# microBoard_HMI.net
KiCad netlist of a schematic drawn in EAGLE
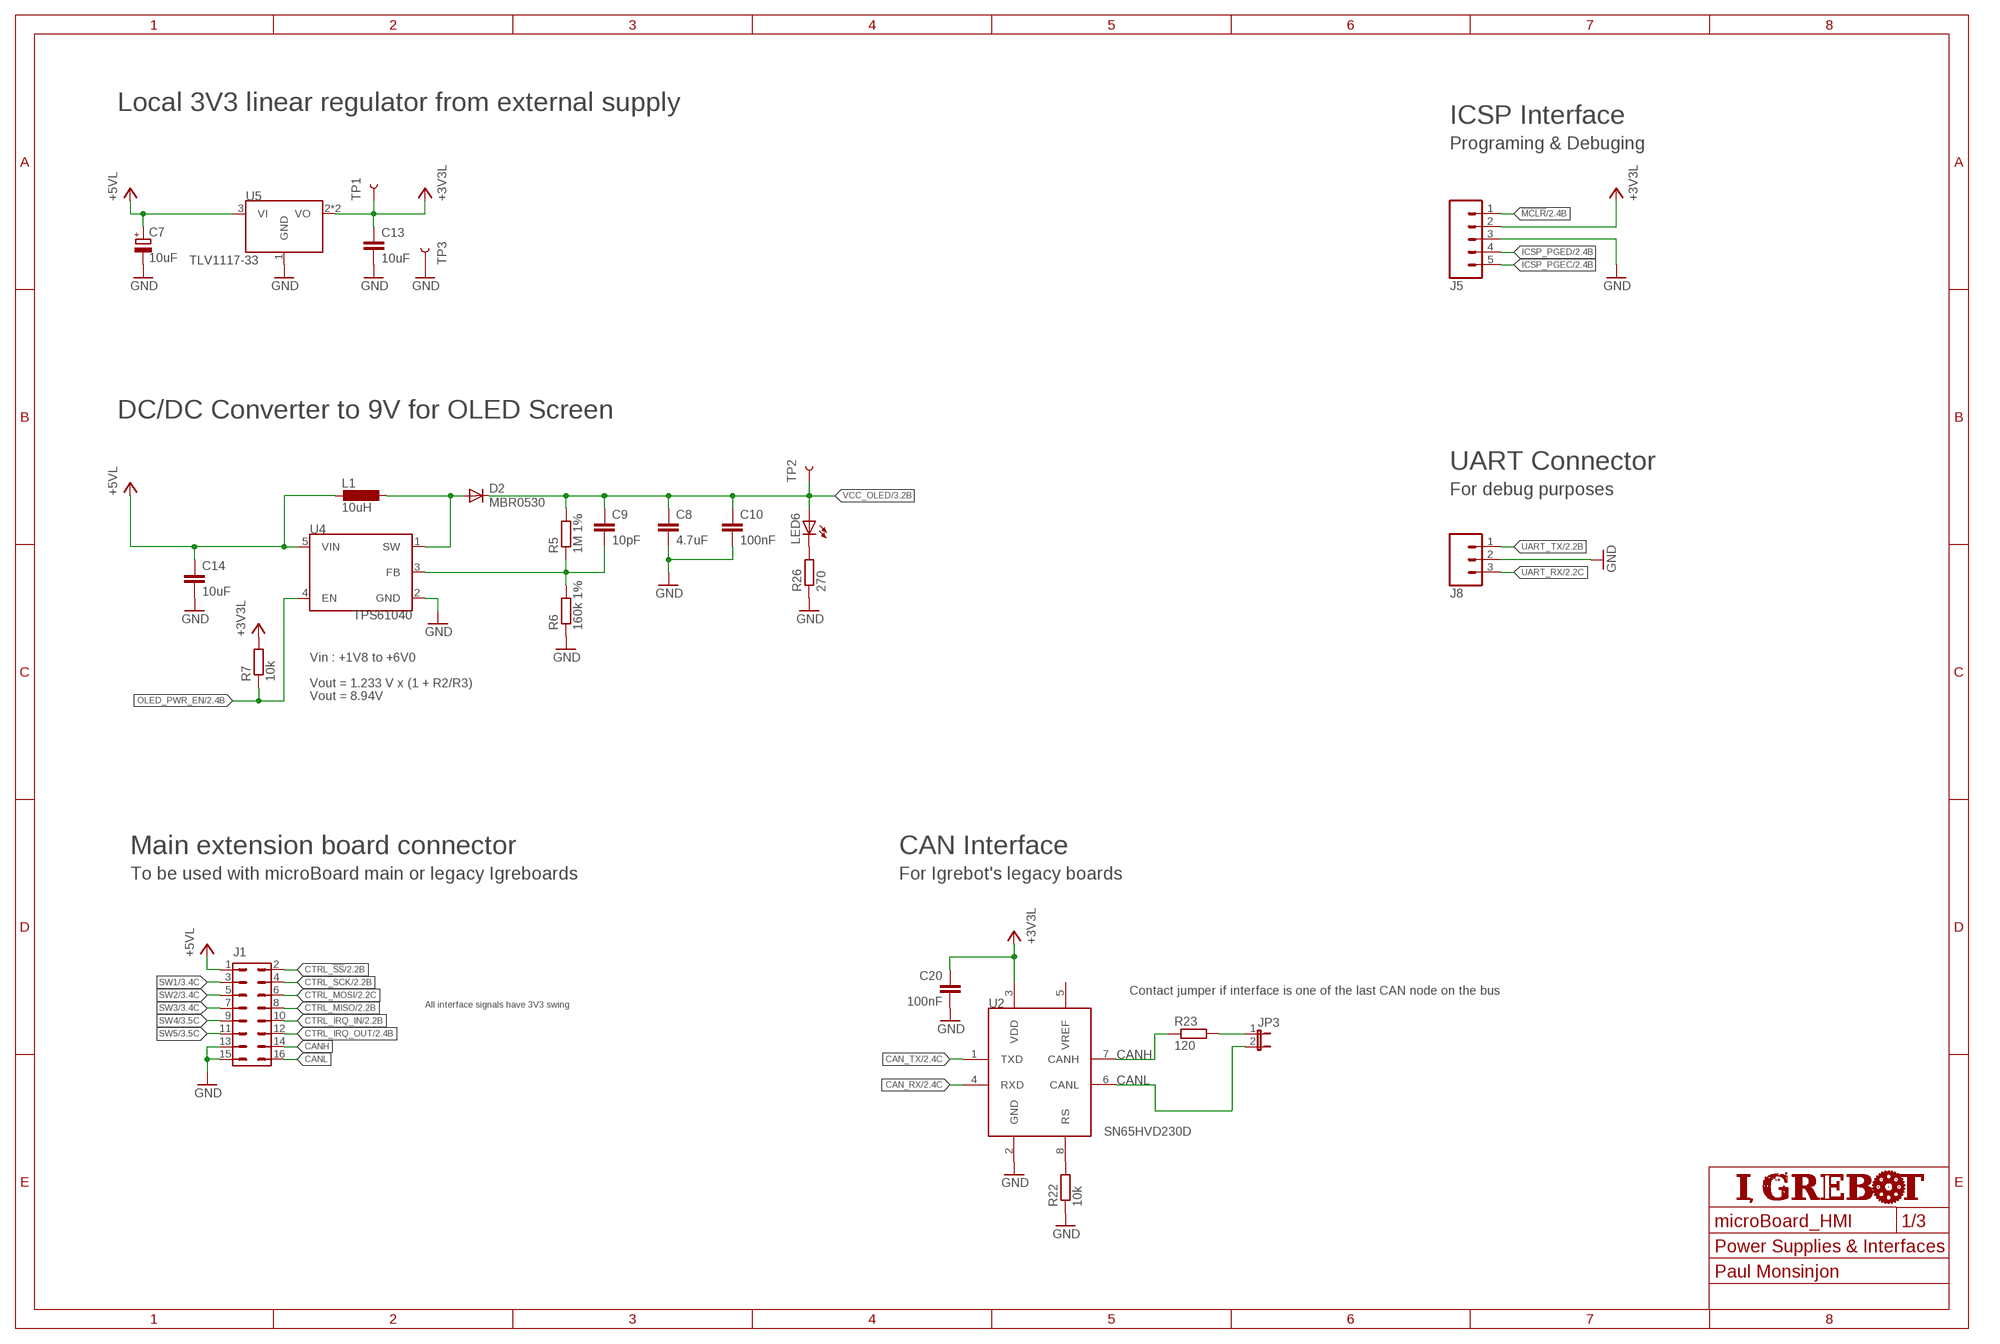
[diagram p0: schematic, sheet 1]
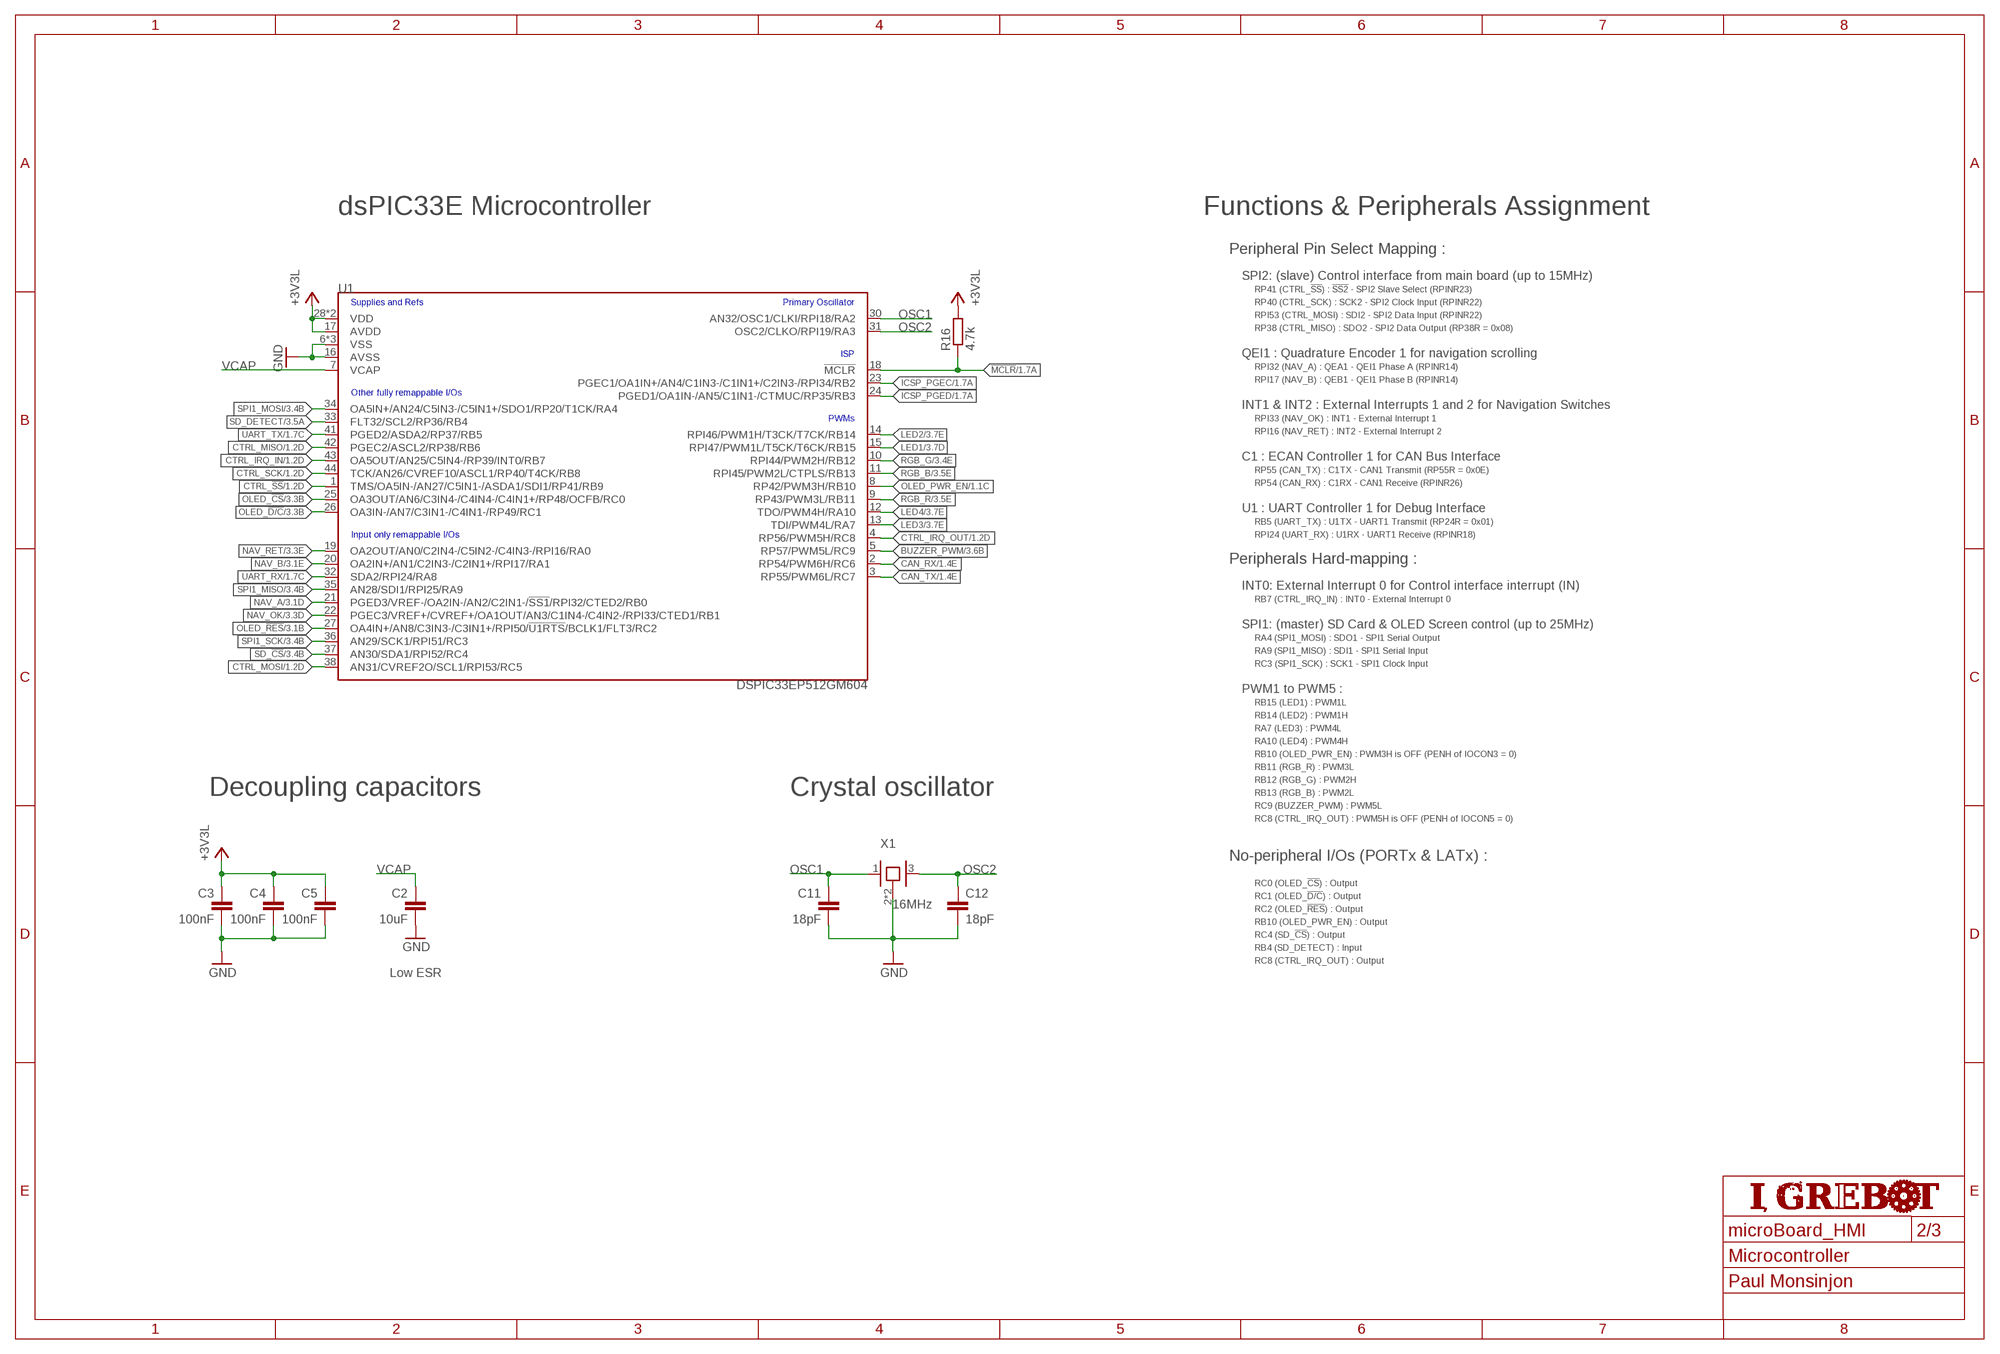
[diagram p1: schematic, sheet 2]
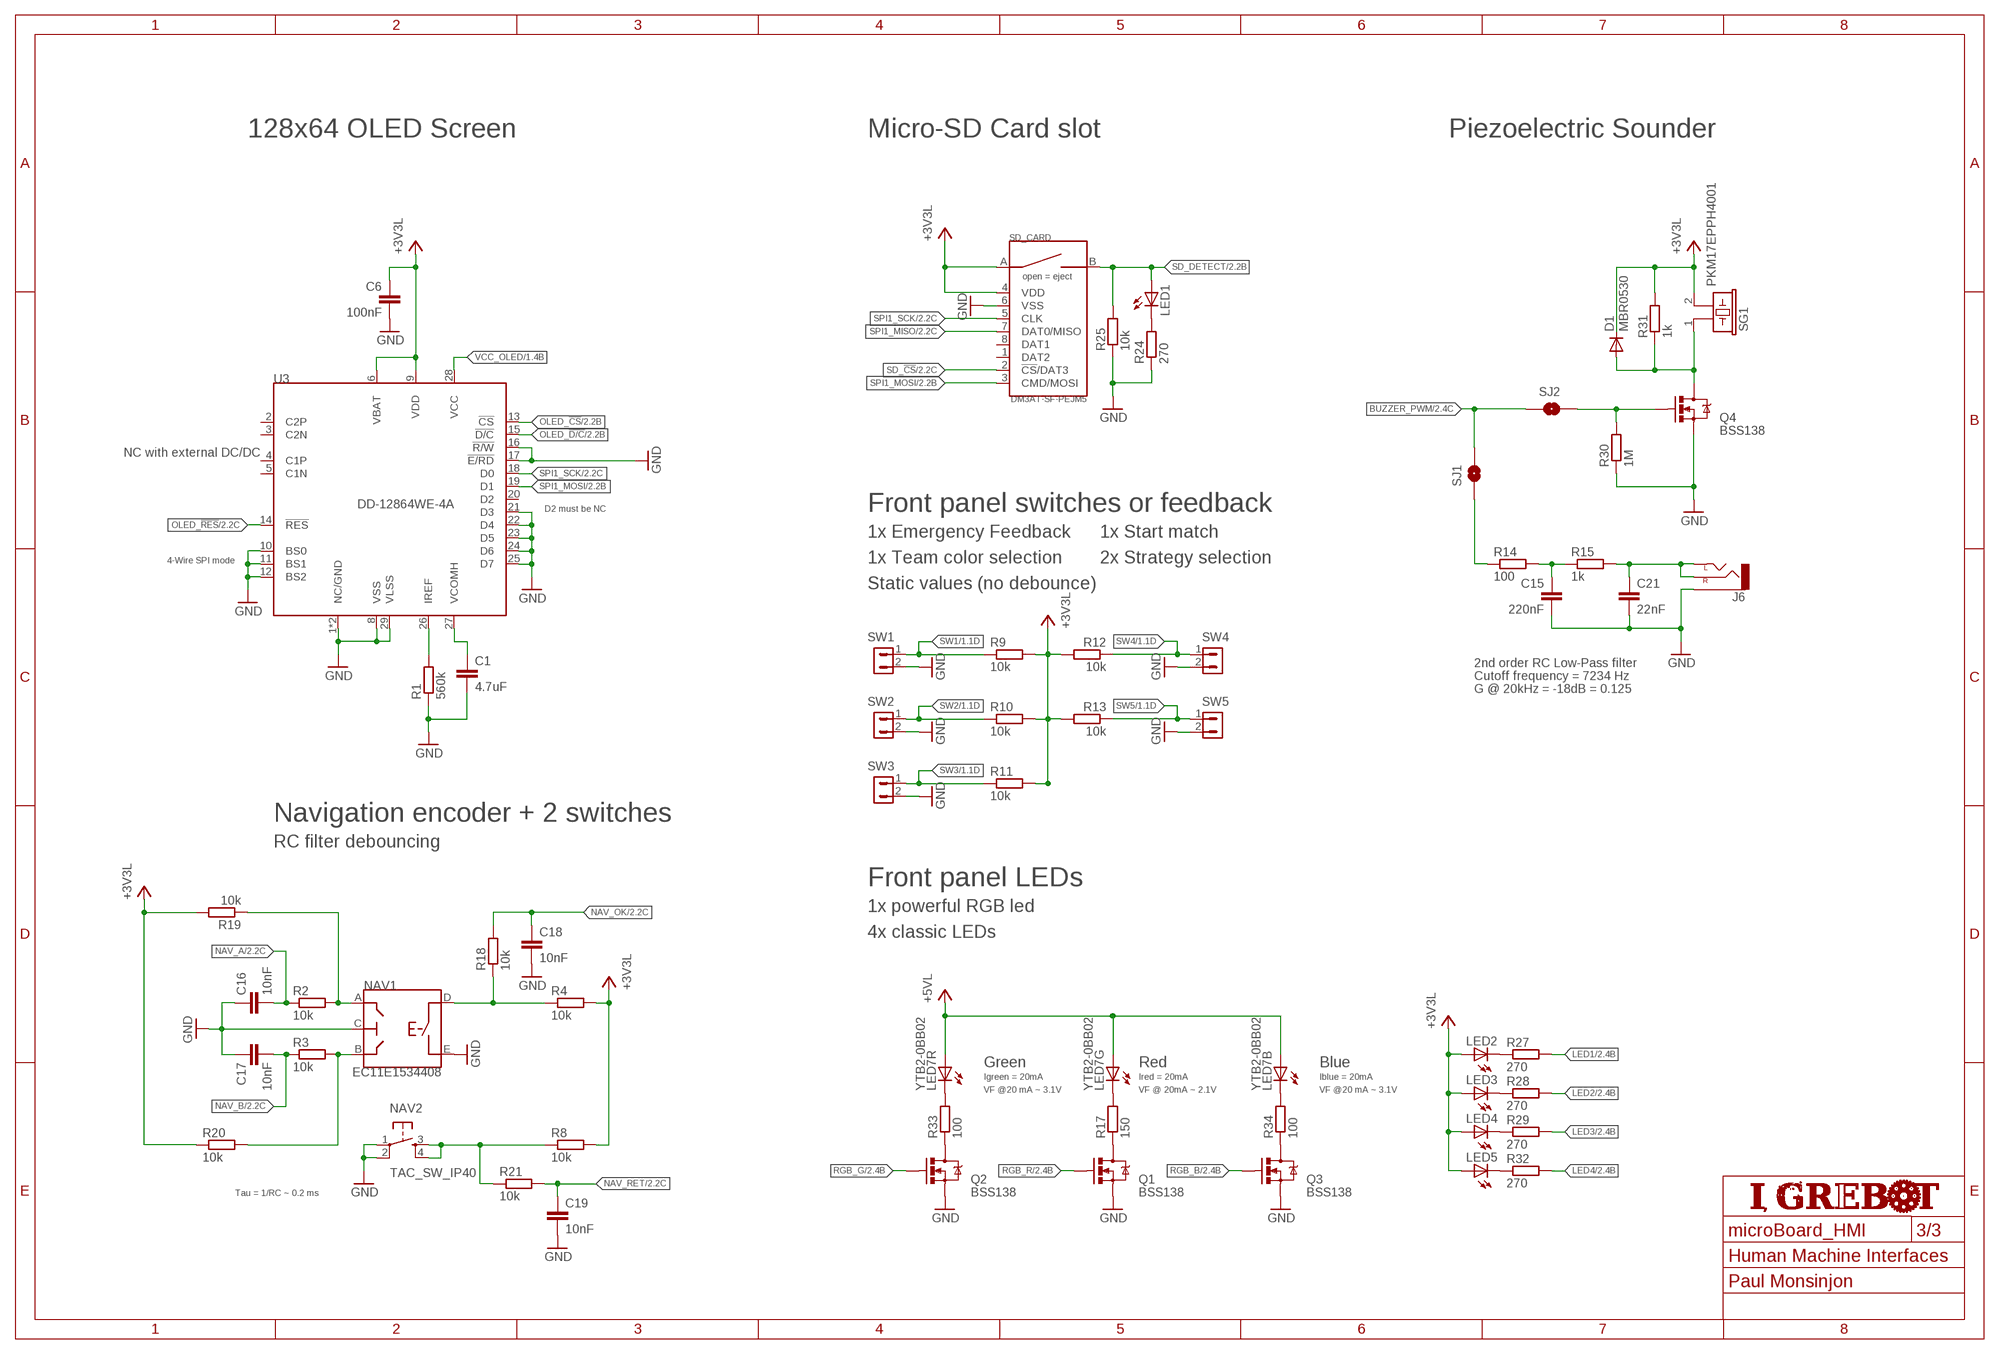
[diagram p2: schematic, sheet 3]

(export (version "E")
  (design (tool "Eeschema 10.0.6"))
  (components
    (comp (ref "C2")
      (value "10uF")
      (footprint "eagle-import:C1206")
      (libsource (lib "eagle-import") (part "C-EUC1206"))
    )
    (comp (ref "C3")
      (value "100nF")
      (footprint "eagle-import:C0603")
      (libsource (lib "eagle-import") (part "C-EUC0603"))
    )
    (comp (ref "C4")
      (value "100nF")
      (footprint "eagle-import:C0603")
      (libsource (lib "eagle-import") (part "C-EUC0603"))
    )
    (comp (ref "C5")
      (value "100nF")
      (footprint "eagle-import:C0603")
      (libsource (lib "eagle-import") (part "C-EUC0603"))
    )
    (comp (ref "C11")
      (value "18pF")
      (footprint "eagle-import:C0603")
      (libsource (lib "eagle-import") (part "C-EUC0603"))
    )
    (comp (ref "C12")
      (value "18pF")
      (footprint "eagle-import:C0603")
      (libsource (lib "eagle-import") (part "C-EUC0603"))
    )
    (comp (ref "R16")
      (value "4.7k")
      (footprint "eagle-import:R0603")
      (libsource (lib "eagle-import") (part "resistor_R-EU_R0603"))
    )
    (comp (ref "U1")
      (value "DSPIC33EP512GM604")
      (footprint "eagle-import:TQFP_44")
      (libsource (lib "eagle-import") (part "DSPIC33EP512GM604"))
    )
    (comp (ref "X1")
      (value "16MHz")
      (footprint "eagle-import:CRYSTAL-OSC-SMD-5X3")
      (libsource (lib "eagle-import") (part "XTAL_5X3"))
    )
    (comp (ref "C1")
      (value "4.7uF")
      (footprint "eagle-import:C1206")
      (libsource (lib "eagle-import") (part "C-EUC1206"))
    )
    (comp (ref "C6")
      (value "100nF")
      (footprint "eagle-import:C0603")
      (libsource (lib "eagle-import") (part "C-EUC0603"))
    )
    (comp (ref "C15")
      (value "220nF")
      (footprint "eagle-import:C0603")
      (libsource (lib "eagle-import") (part "C-EUC0603"))
    )
    (comp (ref "C16")
      (value "10nF")
      (footprint "eagle-import:C0603")
      (libsource (lib "eagle-import") (part "C-EUC0603"))
    )
    (comp (ref "C17")
      (value "10nF")
      (footprint "eagle-import:C0603")
      (libsource (lib "eagle-import") (part "C-EUC0603"))
    )
    (comp (ref "C18")
      (value "10nF")
      (footprint "eagle-import:C0603")
      (libsource (lib "eagle-import") (part "C-EUC0603"))
    )
    (comp (ref "C19")
      (value "10nF")
      (footprint "eagle-import:C0603")
      (libsource (lib "eagle-import") (part "C-EUC0603"))
    )
    (comp (ref "C21")
      (value "22nF")
      (footprint "eagle-import:C0603")
      (libsource (lib "eagle-import") (part "C-EUC0603"))
    )
    (comp (ref "D1")
      (value "MBR0530")
      (footprint "eagle-import:SOD-123_MINI-SMA")
      (libsource (lib "eagle-import") (part "CGRM400-G1"))
    )
    (comp (ref "J6")
      (value "AUDIO-JACK1:1")
      (footprint "eagle-import:STEREOJACK2.5MM")
      (libsource (lib "eagle-import") (part "AUDIO-JACK1{colon}1"))
    )
    (comp (ref "LED1")
      (value "LEDCHIP-LED0805")
      (footprint "eagle-import:CHIP-LED0805")
      (libsource (lib "eagle-import") (part "LEDCHIP-LED0805"))
    )
    (comp (ref "LED2")
      (value "LEDCHIP-LED0805")
      (footprint "eagle-import:CHIP-LED0805")
      (libsource (lib "eagle-import") (part "LEDCHIP-LED0805"))
    )
    (comp (ref "LED3")
      (value "LEDCHIP-LED0805")
      (footprint "eagle-import:CHIP-LED0805")
      (libsource (lib "eagle-import") (part "LEDCHIP-LED0805"))
    )
    (comp (ref "LED4")
      (value "LEDCHIP-LED0805")
      (footprint "eagle-import:CHIP-LED0805")
      (libsource (lib "eagle-import") (part "LEDCHIP-LED0805"))
    )
    (comp (ref "LED5")
      (value "LEDCHIP-LED0805")
      (footprint "eagle-import:CHIP-LED0805")
      (libsource (lib "eagle-import") (part "LEDCHIP-LED0805"))
    )
    (comp (ref "LED7")
      (value "YTB2-0BB02")
      (footprint "eagle-import:GM5WA94310A")
      (libsource (lib "eagle-import") (part "GM5WA94310A"))
    )
    (comp (ref "NAV1")
      (value "EC11E1534408")
      (footprint "eagle-import:EC11E1534408")
      (libsource (lib "eagle-import") (part "EC11E1534408"))
    )
    (comp (ref "NAV2")
      (value "TAC_SW_IP40")
      (footprint "eagle-import:TAC_SW_IP40")
      (libsource (lib "eagle-import") (part "TAC_SW_IP40"))
    )
    (comp (ref "Q1")
      (value "BSS138")
      (footprint "eagle-import:SOT23")
      (libsource (lib "eagle-import") (part "MOSFET-NCHANNELBSS138"))
    )
    (comp (ref "Q2")
      (value "BSS138")
      (footprint "eagle-import:SOT23")
      (libsource (lib "eagle-import") (part "MOSFET-NCHANNELBSS138"))
    )
    (comp (ref "Q3")
      (value "BSS138")
      (footprint "eagle-import:SOT23")
      (libsource (lib "eagle-import") (part "MOSFET-NCHANNELBSS138"))
    )
    (comp (ref "Q4")
      (value "BSS138")
      (footprint "eagle-import:SOT23")
      (fields (field (name "PROD_ID") "TRANS-00830"))
      (libsource (lib "eagle-import") (part "MOSFET-NCHANNELBSS138"))
    )
    (comp (ref "R1")
      (value "560k")
      (footprint "eagle-import:R0603")
      (libsource (lib "eagle-import") (part "R-EU_R0603"))
    )
    (comp (ref "R2")
      (value "10k")
      (footprint "eagle-import:R0603")
      (libsource (lib "eagle-import") (part "R-EU_R0603"))
    )
    (comp (ref "R3")
      (value "10k")
      (footprint "eagle-import:R0603")
      (libsource (lib "eagle-import") (part "R-EU_R0603"))
    )
    (comp (ref "R4")
      (value "10k")
      (footprint "eagle-import:R0603")
      (libsource (lib "eagle-import") (part "R-EU_R0603"))
    )
    (comp (ref "R8")
      (value "10k")
      (footprint "eagle-import:R0603")
      (libsource (lib "eagle-import") (part "R-EU_R0603"))
    )
    (comp (ref "R9")
      (value "10k")
      (footprint "eagle-import:R0603")
      (libsource (lib "eagle-import") (part "R-EU_R0603"))
    )
    (comp (ref "R10")
      (value "10k")
      (footprint "eagle-import:R0603")
      (libsource (lib "eagle-import") (part "R-EU_R0603"))
    )
    (comp (ref "R11")
      (value "10k")
      (footprint "eagle-import:R0603")
      (libsource (lib "eagle-import") (part "R-EU_R0603"))
    )
    (comp (ref "R12")
      (value "10k")
      (footprint "eagle-import:R0603")
      (libsource (lib "eagle-import") (part "R-EU_R0603"))
    )
    (comp (ref "R13")
      (value "10k")
      (footprint "eagle-import:R0603")
      (libsource (lib "eagle-import") (part "R-EU_R0603"))
    )
    (comp (ref "R14")
      (value "100")
      (footprint "eagle-import:R0603")
      (libsource (lib "eagle-import") (part "resistor_R-EU_R0603"))
    )
    (comp (ref "R15")
      (value "1k")
      (footprint "eagle-import:R0603")
      (libsource (lib "eagle-import") (part "resistor_R-EU_R0603"))
    )
    (comp (ref "R17")
      (value "150")
      (footprint "eagle-import:R0603")
      (libsource (lib "eagle-import") (part "resistor_R-EU_R0603"))
    )
    (comp (ref "R18")
      (value "10k")
      (footprint "eagle-import:R0603")
      (libsource (lib "eagle-import") (part "R-EU_R0603"))
    )
    (comp (ref "R19")
      (value "10k")
      (footprint "eagle-import:R0603")
      (libsource (lib "eagle-import") (part "R-EU_R0603"))
    )
    (comp (ref "R20")
      (value "10k")
      (footprint "eagle-import:R0603")
      (libsource (lib "eagle-import") (part "R-EU_R0603"))
    )
    (comp (ref "R21")
      (value "10k")
      (footprint "eagle-import:R0603")
      (libsource (lib "eagle-import") (part "R-EU_R0603"))
    )
    (comp (ref "R24")
      (value "270")
      (footprint "eagle-import:R0603")
      (libsource (lib "eagle-import") (part "resistor_R-EU_R0603"))
    )
    (comp (ref "R25")
      (value "10k")
      (footprint "eagle-import:R0603")
      (libsource (lib "eagle-import") (part "resistor_R-EU_R0603"))
    )
    (comp (ref "R27")
      (value "270")
      (footprint "eagle-import:R0603")
      (libsource (lib "eagle-import") (part "resistor_R-EU_R0603"))
    )
    (comp (ref "R28")
      (value "270")
      (footprint "eagle-import:R0603")
      (libsource (lib "eagle-import") (part "resistor_R-EU_R0603"))
    )
    (comp (ref "R29")
      (value "270")
      (footprint "eagle-import:R0603")
      (libsource (lib "eagle-import") (part "resistor_R-EU_R0603"))
    )
    (comp (ref "R30")
      (value "1M")
      (footprint "eagle-import:R0603")
      (libsource (lib "eagle-import") (part "resistor_R-EU_R0603"))
    )
    (comp (ref "R31")
      (value "1k")
      (footprint "eagle-import:R0603")
      (libsource (lib "eagle-import") (part "resistor_R-EU_R0603"))
    )
    (comp (ref "R32")
      (value "270")
      (footprint "eagle-import:R0603")
      (libsource (lib "eagle-import") (part "resistor_R-EU_R0603"))
    )
    (comp (ref "R33")
      (value "100")
      (footprint "eagle-import:R0603")
      (libsource (lib "eagle-import") (part "resistor_R-EU_R0603"))
    )
    (comp (ref "R34")
      (value "100")
      (footprint "eagle-import:R0603")
      (libsource (lib "eagle-import") (part "resistor_R-EU_R0603"))
    )
    (comp (ref "SD_CARD")
      (value "DM3AT-SF-PEJM5")
      (footprint "eagle-import:DM3AT")
      (libsource (lib "eagle-import") (part "DM3AT-SF-PEJM5"))
    )
    (comp (ref "SG1")
      (value "PKM17EPPH4001")
      (footprint "eagle-import:F_EE17P")
      (libsource (lib "eagle-import") (part "F/EE17P"))
    )
    (comp (ref "SJ1")
      (value "SOLDERJUMPERNC2")
      (footprint "eagle-import:SJ_2S-NOTRACE")
      (libsource (lib "eagle-import") (part "SOLDERJUMPERNC2"))
    )
    (comp (ref "SJ2")
      (value "SOLDERJUMPERNC2")
      (footprint "eagle-import:SJ_2S-NOTRACE")
      (libsource (lib "eagle-import") (part "SOLDERJUMPERNC2"))
    )
    (comp (ref "SW1")
      (value "HE14_H_2")
      (footprint "eagle-import:HE14_H_2")
      (libsource (lib "eagle-import") (part "HE14_H_2"))
    )
    (comp (ref "SW2")
      (value "HE14_H_2")
      (footprint "eagle-import:HE14_H_2")
      (libsource (lib "eagle-import") (part "HE14_H_2"))
    )
    (comp (ref "SW3")
      (value "HE14_H_2")
      (footprint "eagle-import:HE14_H_2")
      (libsource (lib "eagle-import") (part "HE14_H_2"))
    )
    (comp (ref "SW4")
      (value "HE14_H_2")
      (footprint "eagle-import:HE14_H_2")
      (libsource (lib "eagle-import") (part "HE14_H_2"))
    )
    (comp (ref "SW5")
      (value "HE14_H_2")
      (footprint "eagle-import:HE14_H_2")
      (libsource (lib "eagle-import") (part "HE14_H_2"))
    )
    (comp (ref "U3")
      (value "DD-12864WE-4A")
      (footprint "eagle-import:DD-12864WE-4A")
      (libsource (lib "eagle-import") (part "DD-12864WE-4A"))
    )
    (comp (ref "C7")
      (value "10uF")
      (footprint "eagle-import:PANASONIC_C")
      (libsource (lib "eagle-import") (part "CPOL-EUC"))
    )
    (comp (ref "C8")
      (value "4.7uF")
      (footprint "eagle-import:C1206")
      (libsource (lib "eagle-import") (part "C-EUC1206"))
    )
    (comp (ref "C9")
      (value "10pF")
      (footprint "eagle-import:C0603")
      (libsource (lib "eagle-import") (part "C-EUC0603"))
    )
    (comp (ref "C10")
      (value "100nF")
      (footprint "eagle-import:C0603")
      (libsource (lib "eagle-import") (part "C-EUC0603"))
    )
    (comp (ref "C13")
      (value "10uF")
      (footprint "eagle-import:C1206")
      (libsource (lib "eagle-import") (part "C-EUC1206"))
    )
    (comp (ref "C14")
      (value "10uF")
      (footprint "eagle-import:C1206")
      (libsource (lib "eagle-import") (part "C-EUC1206"))
    )
    (comp (ref "C20")
      (value "100nF")
      (footprint "eagle-import:C0603")
      (libsource (lib "eagle-import") (part "C-EUC0603"))
    )
    (comp (ref "D2")
      (value "MBR0530")
      (footprint "eagle-import:SOD-123_MINI-SMA")
      (libsource (lib "eagle-import") (part "CGRM400-G1"))
    )
    (comp (ref "J1")
      (value "HE10_H_16")
      (footprint "eagle-import:CON_2X_2.54_H_16")
      (libsource (lib "eagle-import") (part "HE10_H_16"))
    )
    (comp (ref "J5")
      (value "M05LOCK")
      (footprint "eagle-import:1X05_LOCK")
      (libsource (lib "eagle-import") (part "M05LOCK"))
    )
    (comp (ref "J8")
      (value "M03LOCK")
      (footprint "eagle-import:1X03_LOCK")
      (libsource (lib "eagle-import") (part "M03LOCK"))
    )
    (comp (ref "JP3")
      (value "JUMPER-2PTH_LOCK")
      (footprint "eagle-import:1X02_LOCK")
      (libsource (lib "eagle-import") (part "JUMPER-2PTH_LOCK"))
    )
    (comp (ref "L1")
      (value "10uH")
      (footprint "eagle-import:L5650M")
      (libsource (lib "eagle-import") (part "L-EUL5650M"))
    )
    (comp (ref "LED6")
      (value "LEDCHIP-LED0805")
      (footprint "eagle-import:CHIP-LED0805")
      (libsource (lib "eagle-import") (part "LEDCHIP-LED0805"))
    )
    (comp (ref "R5")
      (value "1M 1%")
      (footprint "eagle-import:R0603")
      (libsource (lib "eagle-import") (part "R-EU_R0603"))
    )
    (comp (ref "R6")
      (value "160k 1%")
      (footprint "eagle-import:R0603")
      (libsource (lib "eagle-import") (part "R-EU_R0603"))
    )
    (comp (ref "R7")
      (value "10k")
      (footprint "eagle-import:R0603")
      (libsource (lib "eagle-import") (part "R-EU_R0603"))
    )
    (comp (ref "R22")
      (value "10k")
      (footprint "eagle-import:R0603")
      (libsource (lib "eagle-import") (part "R-EU_R0603"))
    )
    (comp (ref "R23")
      (value "120")
      (footprint "eagle-import:R0603")
      (libsource (lib "eagle-import") (part "R-EU_R0603"))
    )
    (comp (ref "R26")
      (value "270")
      (footprint "eagle-import:R0603")
      (libsource (lib "eagle-import") (part "resistor_R-EU_R0603"))
    )
    (comp (ref "TP1")
      (value "TEST-POINT3X5")
      (footprint "eagle-import:PAD.03X.05")
      (libsource (lib "eagle-import") (part "TEST-POINT3X5"))
    )
    (comp (ref "TP2")
      (value "TEST-POINT3X5")
      (footprint "eagle-import:PAD.03X.05")
      (libsource (lib "eagle-import") (part "TEST-POINT3X5"))
    )
    (comp (ref "TP3")
      (value "TEST-POINT3X5")
      (footprint "eagle-import:PAD.03X.05")
      (libsource (lib "eagle-import") (part "TEST-POINT3X5"))
    )
    (comp (ref "U2")
      (value "SN65HVD230D")
      (footprint "eagle-import:SO-08")
      (libsource (lib "eagle-import") (part "MCP2551"))
    )
    (comp (ref "U4")
      (value "TPS61040")
      (footprint "eagle-import:SOT-23")
      (libsource (lib "eagle-import") (part "TPS61040"))
    )
    (comp (ref "U5")
      (value "TLV1117-33")
      (footprint "eagle-import:SOT_223")
      (libsource (lib "eagle-import") (part "NX1117C"))
    )
  )
  (nets
    (net (code "1") (name "+3V3L") (class "Default")
      (node (ref "C13") (pin "1") (pinfunction "1_1") (pintype "passive"))
      (node (ref "C20") (pin "1") (pinfunction "1_1") (pintype "passive"))
      (node (ref "C3") (pin "1") (pinfunction "1_1") (pintype "passive"))
      (node (ref "C4") (pin "1") (pinfunction "1_1") (pintype "passive"))
      (node (ref "C5") (pin "1") (pinfunction "1_1") (pintype "passive"))
      (node (ref "C6") (pin "1") (pinfunction "1_1") (pintype "passive"))
      (node (ref "D1") (pin "C") (pinfunction "C_C") (pintype "passive"))
      (node (ref "J5") (pin "2") (pinfunction "2_2") (pintype "passive"))
      (node (ref "LED2") (pin "A") (pinfunction "A_A") (pintype "passive"))
      (node (ref "LED3") (pin "A") (pinfunction "A_A") (pintype "passive"))
      (node (ref "LED4") (pin "A") (pinfunction "A_A") (pintype "passive"))
      (node (ref "LED5") (pin "A") (pinfunction "A_A") (pintype "passive"))
      (node (ref "R10") (pin "2") (pinfunction "2_2") (pintype "passive"))
      (node (ref "R11") (pin "2") (pinfunction "2_2") (pintype "passive"))
      (node (ref "R12") (pin "2") (pinfunction "2_2") (pintype "passive"))
      (node (ref "R13") (pin "2") (pinfunction "2_2") (pintype "passive"))
      (node (ref "R16") (pin "2") (pinfunction "2_2") (pintype "passive"))
      (node (ref "R19") (pin "2") (pinfunction "2_2") (pintype "passive"))
      (node (ref "R20") (pin "1") (pinfunction "1_1") (pintype "passive"))
      (node (ref "R31") (pin "2") (pinfunction "2_2") (pintype "passive"))
      (node (ref "R4") (pin "2") (pinfunction "2_2") (pintype "passive"))
      (node (ref "R7") (pin "2") (pinfunction "2_2") (pintype "passive"))
      (node (ref "R8") (pin "2") (pinfunction "2_2") (pintype "passive"))
      (node (ref "R9") (pin "2") (pinfunction "2_2") (pintype "passive"))
      (node (ref "SD_CARD") (pin "4") (pinfunction "VDD_4") (pintype "power_in"))
      (node (ref "SD_CARD") (pin "A") (pinfunction "A_A") (pintype "bidirectional"))
      (node (ref "SG1") (pin "2") (pinfunction "2_2") (pintype "passive"))
      (node (ref "TP1") (pin "P$1") (pinfunction "1_P$1") (pintype "bidirectional"))
      (node (ref "U1") (pin "17") (pinfunction "AVDD_17") (pintype "bidirectional"))
      (node (ref "U1") (pin "28") (pinfunction "VDD_28") (pintype "bidirectional"))
      (node (ref "U1") (pin "40") (pinfunction "VDD_40") (pintype "bidirectional"))
      (node (ref "U2") (pin "3") (pinfunction "VDD_3") (pintype "bidirectional"))
      (node (ref "U3") (pin "6") (pinfunction "VBAT_6") (pintype "bidirectional"))
      (node (ref "U3") (pin "9") (pinfunction "VDD_9") (pintype "bidirectional"))
      (node (ref "U5") (pin "2") (pinfunction "VO_2") (pintype "power_in"))
      (node (ref "U5") (pin "4") (pinfunction "VO_4") (pintype "power_in"))
    )
    (net (code "2") (name "+5VL") (class "Default")
      (node (ref "C14") (pin "1") (pinfunction "1_1") (pintype "passive"))
      (node (ref "C7") (pin "+") (pinfunction "+_+") (pintype "passive"))
      (node (ref "J1") (pin "1") (pinfunction "1_1") (pintype "bidirectional"))
      (node (ref "L1") (pin "2") (pinfunction "2_2") (pintype "passive"))
      (node (ref "LED7") (pin "1") (pinfunction "A_1") (pintype "passive"))
      (node (ref "LED7") (pin "2") (pinfunction "A_2") (pintype "passive"))
      (node (ref "LED7") (pin "3") (pinfunction "A_3") (pintype "passive"))
      (node (ref "U4") (pin "5") (pinfunction "VIN_5") (pintype "bidirectional"))
      (node (ref "U5") (pin "3") (pinfunction "VI_3") (pintype "power_in"))
    )
    (net (code "3") (name "BUZZER_PWM") (class "Default")
      (node (ref "SJ1") (pin "2") (pinfunction "2_2") (pintype "passive"))
      (node (ref "SJ2") (pin "1") (pinfunction "1_1") (pintype "passive"))
      (node (ref "U1") (pin "5") (pinfunction "RP57/PWM5L/RC9_5") (pintype "bidirectional"))
    )
    (net (code "4") (name "CANH") (class "Default")
      (node (ref "J1") (pin "14") (pinfunction "14_14") (pintype "bidirectional"))
      (node (ref "R23") (pin "1") (pinfunction "1_1") (pintype "passive"))
      (node (ref "U2") (pin "7") (pinfunction "CANH_7") (pintype "bidirectional"))
    )
    (net (code "5") (name "CANL") (class "Default")
      (node (ref "J1") (pin "16") (pinfunction "16_16") (pintype "bidirectional"))
      (node (ref "JP3") (pin "2") (pinfunction "2_2") (pintype "passive"))
      (node (ref "U2") (pin "6") (pinfunction "CANL_6") (pintype "bidirectional"))
    )
    (net (code "6") (name "CAN_RX") (class "Default")
      (node (ref "U1") (pin "2") (pinfunction "RP54/PWM6H/RC6_2") (pintype "bidirectional"))
      (node (ref "U2") (pin "4") (pinfunction "RXD_4") (pintype "bidirectional"))
    )
    (net (code "7") (name "CAN_TX") (class "Default")
      (node (ref "U1") (pin "3") (pinfunction "RP55/PWM6L/RC7_3") (pintype "bidirectional"))
      (node (ref "U2") (pin "1") (pinfunction "TXD_1") (pintype "bidirectional"))
    )
    (net (code "8") (name "CTRL_IRQ_IN") (class "Default")
      (node (ref "J1") (pin "10") (pinfunction "10_10") (pintype "bidirectional"))
      (node (ref "U1") (pin "43") (pinfunction "OA5OUT/AN25/C5IN4-/RP39/INT0/RB7_43") (pintype "bidirectional"))
    )
    (net (code "9") (name "CTRL_IRQ_OUT") (class "Default")
      (node (ref "J1") (pin "12") (pinfunction "12_12") (pintype "bidirectional"))
      (node (ref "U1") (pin "4") (pinfunction "RP56/PWM5H/RC8_4") (pintype "bidirectional"))
    )
    (net (code "10") (name "CTRL_MISO") (class "Default")
      (node (ref "J1") (pin "8") (pinfunction "8_8") (pintype "bidirectional"))
      (node (ref "U1") (pin "42") (pinfunction "PGEC2/ASCL2/RP38/RB6_42") (pintype "bidirectional"))
    )
    (net (code "11") (name "CTRL_MOSI") (class "Default")
      (node (ref "J1") (pin "6") (pinfunction "6_6") (pintype "bidirectional"))
      (node (ref "U1") (pin "38") (pinfunction "AN31/CVREF2O/SCL1/RPI53/RC5_38") (pintype "bidirectional"))
    )
    (net (code "12") (name "CTRL_SCK") (class "Default")
      (node (ref "J1") (pin "4") (pinfunction "4_4") (pintype "bidirectional"))
      (node (ref "U1") (pin "44") (pinfunction "TCK/AN26/CVREF10/ASCL1/RP40/T4CK/RB8_44") (pintype "bidirectional"))
    )
    (net (code "13") (name "CTRL_~{SS}") (class "Default")
      (node (ref "J1") (pin "2") (pinfunction "2_2") (pintype "bidirectional"))
      (node (ref "U1") (pin "1") (pinfunction "TMS/OA5IN-/AN27/C5IN1-/ASDA1/SDI1/RP41/RB9_1") (pintype "bidirectional"))
    )
    (net (code "14") (name "GND") (class "Default")
      (node (ref "C1") (pin "2") (pinfunction "2_2") (pintype "passive"))
      (node (ref "C10") (pin "2") (pinfunction "2_2") (pintype "passive"))
      (node (ref "C11") (pin "2") (pinfunction "2_2") (pintype "passive"))
      (node (ref "C12") (pin "2") (pinfunction "2_2") (pintype "passive"))
      (node (ref "C13") (pin "2") (pinfunction "2_2") (pintype "passive"))
      (node (ref "C14") (pin "2") (pinfunction "2_2") (pintype "passive"))
      (node (ref "C15") (pin "2") (pinfunction "2_2") (pintype "passive"))
      (node (ref "C16") (pin "1") (pinfunction "1_1") (pintype "passive"))
      (node (ref "C17") (pin "1") (pinfunction "1_1") (pintype "passive"))
      (node (ref "C18") (pin "2") (pinfunction "2_2") (pintype "passive"))
      (node (ref "C19") (pin "2") (pinfunction "2_2") (pintype "passive"))
      (node (ref "C2") (pin "2") (pinfunction "2_2") (pintype "passive"))
      (node (ref "C20") (pin "2") (pinfunction "2_2") (pintype "passive"))
      (node (ref "C21") (pin "2") (pinfunction "2_2") (pintype "passive"))
      (node (ref "C3") (pin "2") (pinfunction "2_2") (pintype "passive"))
      (node (ref "C4") (pin "2") (pinfunction "2_2") (pintype "passive"))
      (node (ref "C5") (pin "2") (pinfunction "2_2") (pintype "passive"))
      (node (ref "C6") (pin "2") (pinfunction "2_2") (pintype "passive"))
      (node (ref "C7") (pin "-") (pinfunction "-_-") (pintype "passive"))
      (node (ref "C8") (pin "2") (pinfunction "2_2") (pintype "passive"))
      (node (ref "J1") (pin "13") (pinfunction "13_13") (pintype "bidirectional"))
      (node (ref "J1") (pin "15") (pinfunction "15_15") (pintype "bidirectional"))
      (node (ref "J5") (pin "3") (pinfunction "3_3") (pintype "passive"))
      (node (ref "J6") (pin "5") (pinfunction "SLEEVE_5") (pintype "bidirectional"))
      (node (ref "J8") (pin "2") (pinfunction "2_2") (pintype "passive"))
      (node (ref "NAV1") (pin "C") (pinfunction "C_C") (pintype "bidirectional"))
      (node (ref "NAV1") (pin "E") (pinfunction "E_E") (pintype "bidirectional"))
      (node (ref "NAV2") (pin "1") (pinfunction "1_1") (pintype "passive"))
      (node (ref "NAV2") (pin "2") (pinfunction "2_2") (pintype "passive"))
      (node (ref "Q1") (pin "2") (pinfunction "S_2") (pintype "passive"))
      (node (ref "Q2") (pin "2") (pinfunction "S_2") (pintype "passive"))
      (node (ref "Q3") (pin "2") (pinfunction "S_2") (pintype "passive"))
      (node (ref "Q4") (pin "2") (pinfunction "S_2") (pintype "passive"))
      (node (ref "R1") (pin "1") (pinfunction "1_1") (pintype "passive"))
      (node (ref "R22") (pin "1") (pinfunction "1_1") (pintype "passive"))
      (node (ref "R24") (pin "1") (pinfunction "1_1") (pintype "passive"))
      (node (ref "R25") (pin "1") (pinfunction "1_1") (pintype "passive"))
      (node (ref "R26") (pin "1") (pinfunction "1_1") (pintype "passive"))
      (node (ref "R30") (pin "1") (pinfunction "1_1") (pintype "passive"))
      (node (ref "R6") (pin "1") (pinfunction "1_1") (pintype "passive"))
      (node (ref "SD_CARD") (pin "6") (pinfunction "VSS_6") (pintype "power_in"))
      (node (ref "SW1") (pin "2") (pinfunction "2_2") (pintype "bidirectional"))
      (node (ref "SW2") (pin "2") (pinfunction "2_2") (pintype "bidirectional"))
      (node (ref "SW3") (pin "2") (pinfunction "2_2") (pintype "bidirectional"))
      (node (ref "SW4") (pin "2") (pinfunction "2_2") (pintype "bidirectional"))
      (node (ref "SW5") (pin "2") (pinfunction "2_2") (pintype "bidirectional"))
      (node (ref "TP3") (pin "P$1") (pinfunction "1_P$1") (pintype "bidirectional"))
      (node (ref "U1") (pin "16") (pinfunction "AVSS_16") (pintype "bidirectional"))
      (node (ref "U1") (pin "29") (pinfunction "VSS_29") (pintype "bidirectional"))
      (node (ref "U1") (pin "39") (pinfunction "VSS_39") (pintype "bidirectional"))
      (node (ref "U1") (pin "6") (pinfunction "VSS_6") (pintype "bidirectional"))
      (node (ref "U2") (pin "2") (pinfunction "GND_2") (pintype "bidirectional"))
      (node (ref "U3") (pin "1") (pinfunction "NC/GND_1") (pintype "bidirectional"))
      (node (ref "U3") (pin "10") (pinfunction "BS0_10") (pintype "bidirectional"))
      (node (ref "U3") (pin "11") (pinfunction "BS1_11") (pintype "bidirectional"))
      (node (ref "U3") (pin "12") (pinfunction "BS2_12") (pintype "bidirectional"))
      (node (ref "U3") (pin "16") (pinfunction "~{R/W}_16") (pintype "bidirectional"))
      (node (ref "U3") (pin "17") (pinfunction "~{E/RD}_17") (pintype "bidirectional"))
      (node (ref "U3") (pin "21") (pinfunction "D3_21") (pintype "bidirectional"))
      (node (ref "U3") (pin "22") (pinfunction "D4_22") (pintype "bidirectional"))
      (node (ref "U3") (pin "23") (pinfunction "D5_23") (pintype "bidirectional"))
      (node (ref "U3") (pin "24") (pinfunction "D6_24") (pintype "bidirectional"))
      (node (ref "U3") (pin "25") (pinfunction "D7_25") (pintype "bidirectional"))
      (node (ref "U3") (pin "29") (pinfunction "VLSS_29") (pintype "bidirectional"))
      (node (ref "U3") (pin "30") (pinfunction "NC/GND_30") (pintype "bidirectional"))
      (node (ref "U3") (pin "8") (pinfunction "VSS_8") (pintype "bidirectional"))
      (node (ref "U4") (pin "2") (pinfunction "GND_2") (pintype "bidirectional"))
      (node (ref "U5") (pin "1") (pinfunction "GND_1") (pintype "power_in"))
      (node (ref "X1") (pin "2") (pinfunction "P$3_2") (pintype "bidirectional"))
      (node (ref "X1") (pin "4") (pinfunction "P$3_4") (pintype "bidirectional"))
    )
    (net (code "15") (name "ICSP_PGEC") (class "Default")
      (node (ref "J5") (pin "5") (pinfunction "5_5") (pintype "passive"))
      (node (ref "U1") (pin "23") (pinfunction "PGEC1/OA1IN+/AN4/C1IN3-/C1IN1+/C2IN3-/RPI34/RB2_23") (pintype "bidirectional"))
    )
    (net (code "16") (name "ICSP_PGED") (class "Default")
      (node (ref "J5") (pin "4") (pinfunction "4_4") (pintype "passive"))
      (node (ref "U1") (pin "24") (pinfunction "PGED1/OA1IN-/AN5/C1IN1-/CTMUC/RP35/RB3_24") (pintype "bidirectional"))
    )
    (net (code "17") (name "LED1") (class "Default")
      (node (ref "R27") (pin "2") (pinfunction "2_2") (pintype "passive"))
      (node (ref "U1") (pin "15") (pinfunction "RPI47/PWM1L/T5CK/T6CK/RB15_15") (pintype "bidirectional"))
    )
    (net (code "18") (name "LED2") (class "Default")
      (node (ref "R28") (pin "2") (pinfunction "2_2") (pintype "passive"))
      (node (ref "U1") (pin "14") (pinfunction "RPI46/PWM1H/T3CK/T7CK/RB14_14") (pintype "bidirectional"))
    )
    (net (code "19") (name "LED3") (class "Default")
      (node (ref "R29") (pin "2") (pinfunction "2_2") (pintype "passive"))
      (node (ref "U1") (pin "13") (pinfunction "TDI/PWM4L/RA7_13") (pintype "bidirectional"))
    )
    (net (code "20") (name "LED4") (class "Default")
      (node (ref "R32") (pin "2") (pinfunction "2_2") (pintype "passive"))
      (node (ref "U1") (pin "12") (pinfunction "TDO/PWM4H/RA10_12") (pintype "bidirectional"))
    )
    (net (code "21") (name "NAV_A") (class "Default")
      (node (ref "C16") (pin "2") (pinfunction "2_2") (pintype "passive"))
      (node (ref "R2") (pin "1") (pinfunction "1_1") (pintype "passive"))
      (node (ref "U1") (pin "21") (pinfunction "PGED3/VREF-/OA2IN-/AN2/C2IN1-/~{SS1}/RPI32/CTED2/RB0_21") (pintype "bidirectional"))
    )
    (net (code "22") (name "NAV_B") (class "Default")
      (node (ref "C17") (pin "2") (pinfunction "2_2") (pintype "passive"))
      (node (ref "R3") (pin "1") (pinfunction "1_1") (pintype "passive"))
      (node (ref "U1") (pin "20") (pinfunction "OA2IN+/AN1/C2IN3-/C2IN1+/RPI17/RA1_20") (pintype "bidirectional"))
    )
    (net (code "23") (name "NAV_OK") (class "Default")
      (node (ref "C18") (pin "1") (pinfunction "1_1") (pintype "passive"))
      (node (ref "R18") (pin "2") (pinfunction "2_2") (pintype "passive"))
      (node (ref "U1") (pin "22") (pinfunction "PGEC3/VREF+/CVREF+/OA1OUT/AN3/C1IN4-/C4IN2-/RPI33/CTED1/RB1_22") (pintype "bidirectional"))
    )
    (net (code "24") (name "NAV_RET") (class "Default")
      (node (ref "C19") (pin "1") (pinfunction "1_1") (pintype "passive"))
      (node (ref "R21") (pin "2") (pinfunction "2_2") (pintype "passive"))
      (node (ref "U1") (pin "19") (pinfunction "OA2OUT/AN0/C2IN4-/C5IN2-/C4IN3-/RPI16/RA0_19") (pintype "bidirectional"))
    )
    (net (code "25") (name "Net-(C15-Pad1)") (class "Default")
      (node (ref "C15") (pin "1") (pinfunction "1_1") (pintype "passive"))
      (node (ref "R14") (pin "2") (pinfunction "2_2") (pintype "passive"))
      (node (ref "R15") (pin "1") (pinfunction "1_1") (pintype "passive"))
    )
    (net (code "26") (name "Net-(J6-LEFT)") (class "Default")
      (node (ref "C21") (pin "1") (pinfunction "1_1") (pintype "passive"))
      (node (ref "J6") (pin "1") (pinfunction "LEFT_1") (pintype "bidirectional"))
      (node (ref "J6") (pin "4") (pinfunction "RIGHT_4") (pintype "bidirectional"))
      (node (ref "R15") (pin "2") (pinfunction "2_2") (pintype "passive"))
    )
    (net (code "27") (name "Net-(JP3-Pad1)") (class "Default")
      (node (ref "JP3") (pin "1") (pinfunction "1_1") (pintype "passive"))
      (node (ref "R23") (pin "2") (pinfunction "2_2") (pintype "passive"))
    )
    (net (code "28") (name "Net-(LED1-PadC)") (class "Default")
      (node (ref "LED1") (pin "C") (pinfunction "C_C") (pintype "passive"))
      (node (ref "R24") (pin "2") (pinfunction "2_2") (pintype "passive"))
    )
    (net (code "29") (name "Net-(LED2-PadC)") (class "Default")
      (node (ref "LED2") (pin "C") (pinfunction "C_C") (pintype "passive"))
      (node (ref "R27") (pin "1") (pinfunction "1_1") (pintype "passive"))
    )
    (net (code "30") (name "Net-(LED3-PadC)") (class "Default")
      (node (ref "LED3") (pin "C") (pinfunction "C_C") (pintype "passive"))
      (node (ref "R28") (pin "1") (pinfunction "1_1") (pintype "passive"))
    )
    (net (code "31") (name "Net-(LED4-PadC)") (class "Default")
      (node (ref "LED4") (pin "C") (pinfunction "C_C") (pintype "passive"))
      (node (ref "R29") (pin "1") (pinfunction "1_1") (pintype "passive"))
    )
    (net (code "32") (name "Net-(LED5-PadC)") (class "Default")
      (node (ref "LED5") (pin "C") (pinfunction "C_C") (pintype "passive"))
      (node (ref "R32") (pin "1") (pinfunction "1_1") (pintype "passive"))
    )
    (net (code "33") (name "Net-(LED6-PadC)") (class "Default")
      (node (ref "LED6") (pin "C") (pinfunction "C_C") (pintype "passive"))
      (node (ref "R26") (pin "2") (pinfunction "2_2") (pintype "passive"))
    )
    (net (code "34") (name "Net-(LED7A-C)") (class "Default")
      (node (ref "LED7") (pin "6") (pinfunction "C_6") (pintype "passive"))
      (node (ref "R34") (pin "2") (pinfunction "2_2") (pintype "passive"))
    )
    (net (code "35") (name "Net-(LED7B-C)") (class "Default")
      (node (ref "LED7") (pin "4") (pinfunction "C_4") (pintype "passive"))
      (node (ref "R17") (pin "2") (pinfunction "2_2") (pintype "passive"))
    )
    (net (code "36") (name "Net-(LED7C-C)") (class "Default")
      (node (ref "LED7") (pin "5") (pinfunction "C_5") (pintype "passive"))
      (node (ref "R33") (pin "2") (pinfunction "2_2") (pintype "passive"))
    )
    (net (code "37") (name "Net-(NAV1-PadA)") (class "Default")
      (node (ref "NAV1") (pin "A") (pinfunction "A_A") (pintype "bidirectional"))
      (node (ref "R19") (pin "1") (pinfunction "1_1") (pintype "passive"))
      (node (ref "R2") (pin "2") (pinfunction "2_2") (pintype "passive"))
    )
    (net (code "38") (name "Net-(NAV1-PadB)") (class "Default")
      (node (ref "NAV1") (pin "B") (pinfunction "B_B") (pintype "bidirectional"))
      (node (ref "R20") (pin "2") (pinfunction "2_2") (pintype "passive"))
      (node (ref "R3") (pin "2") (pinfunction "2_2") (pintype "passive"))
    )
    (net (code "39") (name "Net-(NAV1-PadD)") (class "Default")
      (node (ref "NAV1") (pin "D") (pinfunction "D_D") (pintype "bidirectional"))
      (node (ref "R18") (pin "1") (pinfunction "1_1") (pintype "passive"))
      (node (ref "R4") (pin "1") (pinfunction "1_1") (pintype "passive"))
    )
    (net (code "40") (name "Net-(NAV2-Pad3)") (class "Default")
      (node (ref "NAV2") (pin "3") (pinfunction "3_3") (pintype "passive"))
      (node (ref "NAV2") (pin "4") (pinfunction "4_4") (pintype "passive"))
      (node (ref "R21") (pin "1") (pinfunction "1_1") (pintype "passive"))
      (node (ref "R8") (pin "1") (pinfunction "1_1") (pintype "passive"))
    )
    (net (code "41") (name "Net-(Q1-D)") (class "Default")
      (node (ref "Q1") (pin "3") (pinfunction "D_3") (pintype "passive"))
      (node (ref "R17") (pin "1") (pinfunction "1_1") (pintype "passive"))
    )
    (net (code "42") (name "Net-(Q2-D)") (class "Default")
      (node (ref "Q2") (pin "3") (pinfunction "D_3") (pintype "passive"))
      (node (ref "R33") (pin "1") (pinfunction "1_1") (pintype "passive"))
    )
    (net (code "43") (name "Net-(Q3-D)") (class "Default")
      (node (ref "Q3") (pin "3") (pinfunction "D_3") (pintype "passive"))
      (node (ref "R34") (pin "1") (pinfunction "1_1") (pintype "passive"))
    )
    (net (code "44") (name "Net-(Q4-D)") (class "Default")
      (node (ref "D1") (pin "A") (pinfunction "A_A") (pintype "passive"))
      (node (ref "Q4") (pin "3") (pinfunction "D_3") (pintype "passive"))
      (node (ref "R31") (pin "1") (pinfunction "1_1") (pintype "passive"))
      (node (ref "SG1") (pin "1") (pinfunction "1_1") (pintype "passive"))
    )
    (net (code "45") (name "Net-(Q4-G)") (class "Default")
      (node (ref "Q4") (pin "1") (pinfunction "G_1") (pintype "passive"))
      (node (ref "R30") (pin "2") (pinfunction "2_2") (pintype "passive"))
      (node (ref "SJ2") (pin "2") (pinfunction "2_2") (pintype "passive"))
    )
    (net (code "46") (name "Net-(R14-Pad1)") (class "Default")
      (node (ref "R14") (pin "1") (pinfunction "1_1") (pintype "passive"))
      (node (ref "SJ1") (pin "1") (pinfunction "1_1") (pintype "passive"))
    )
    (net (code "47") (name "Net-(U2-RS)") (class "Default")
      (node (ref "R22") (pin "2") (pinfunction "2_2") (pintype "passive"))
      (node (ref "U2") (pin "8") (pinfunction "RS_8") (pintype "bidirectional"))
    )
    (net (code "48") (name "Net-(U3-IREF)") (class "Default")
      (node (ref "R1") (pin "2") (pinfunction "2_2") (pintype "passive"))
      (node (ref "U3") (pin "26") (pinfunction "IREF_26") (pintype "bidirectional"))
    )
    (net (code "49") (name "Net-(U3-VCOMH)") (class "Default")
      (node (ref "C1") (pin "1") (pinfunction "1_1") (pintype "passive"))
      (node (ref "U3") (pin "27") (pinfunction "VCOMH_27") (pintype "bidirectional"))
    )
    (net (code "50") (name "Net-(U4-FB)") (class "Default")
      (node (ref "C9") (pin "2") (pinfunction "2_2") (pintype "passive"))
      (node (ref "R5") (pin "1") (pinfunction "1_1") (pintype "passive"))
      (node (ref "R6") (pin "2") (pinfunction "2_2") (pintype "passive"))
      (node (ref "U4") (pin "3") (pinfunction "FB_3") (pintype "bidirectional"))
    )
    (net (code "51") (name "Net-(U4-SW)") (class "Default")
      (node (ref "D2") (pin "A") (pinfunction "A_A") (pintype "passive"))
      (node (ref "L1") (pin "1") (pinfunction "1_1") (pintype "passive"))
      (node (ref "U4") (pin "1") (pinfunction "SW_1") (pintype "bidirectional"))
    )
    (net (code "52") (name "OLED_PWR_EN") (class "Default")
      (node (ref "R7") (pin "1") (pinfunction "1_1") (pintype "passive"))
      (node (ref "U1") (pin "8") (pinfunction "RP42/PWM3H/RB10_8") (pintype "bidirectional"))
      (node (ref "U4") (pin "4") (pinfunction "EN_4") (pintype "bidirectional"))
    )
    (net (code "53") (name "OLED_~{CS}") (class "Default")
      (node (ref "U1") (pin "25") (pinfunction "OA3OUT/AN6/C3IN4-/C4IN4-/C4IN1+/RP48/OCFB/RC0_25") (pintype "bidirectional"))
      (node (ref "U3") (pin "13") (pinfunction "~{CS}_13") (pintype "bidirectional"))
    )
    (net (code "54") (name "OLED_~{D{slash}C}") (class "Default")
      (node (ref "U1") (pin "26") (pinfunction "OA3IN-/AN7/C3IN1-/C4IN1-/RP49/RC1_26") (pintype "bidirectional"))
      (node (ref "U3") (pin "15") (pinfunction "~{D/C}_15") (pintype "bidirectional"))
    )
    (net (code "55") (name "OLED_~{RES}") (class "Default")
      (node (ref "U1") (pin "27") (pinfunction "OA4IN+/AN8/C3IN3-/C3IN1+/RPI50/~{U1RTS}/BCLK1/FLT3/RC2_27") (pintype "bidirectional"))
      (node (ref "U3") (pin "14") (pinfunction "~{RES}_14") (pintype "bidirectional"))
    )
    (net (code "56") (name "OSC1") (class "Default")
      (node (ref "C11") (pin "1") (pinfunction "1_1") (pintype "passive"))
      (node (ref "U1") (pin "30") (pinfunction "AN32/OSC1/CLKI/RPI18/RA2_30") (pintype "bidirectional"))
      (node (ref "X1") (pin "1") (pinfunction "P$1_1") (pintype "bidirectional"))
    )
    (net (code "57") (name "OSC2") (class "Default")
      (node (ref "C12") (pin "1") (pinfunction "1_1") (pintype "passive"))
      (node (ref "U1") (pin "31") (pinfunction "OSC2/CLKO/RPI19/RA3_31") (pintype "bidirectional"))
      (node (ref "X1") (pin "3") (pinfunction "P$2_3") (pintype "bidirectional"))
    )
    (net (code "58") (name "RGB_B") (class "Default")
      (node (ref "Q3") (pin "1") (pinfunction "G_1") (pintype "passive"))
      (node (ref "U1") (pin "11") (pinfunction "RPI45/PWM2L/CTPLS/RB13_11") (pintype "bidirectional"))
    )
    (net (code "59") (name "RGB_G") (class "Default")
      (node (ref "Q2") (pin "1") (pinfunction "G_1") (pintype "passive"))
      (node (ref "U1") (pin "10") (pinfunction "RPI44/PWM2H/RB12_10") (pintype "bidirectional"))
    )
    (net (code "60") (name "RGB_R") (class "Default")
      (node (ref "Q1") (pin "1") (pinfunction "G_1") (pintype "passive"))
      (node (ref "U1") (pin "9") (pinfunction "RP43/PWM3L/RB11_9") (pintype "bidirectional"))
    )
    (net (code "61") (name "SD_DETECT") (class "Default")
      (node (ref "LED1") (pin "A") (pinfunction "A_A") (pintype "passive"))
      (node (ref "R25") (pin "2") (pinfunction "2_2") (pintype "passive"))
      (node (ref "SD_CARD") (pin "B") (pinfunction "B_B") (pintype "bidirectional"))
      (node (ref "U1") (pin "33") (pinfunction "FLT32/SCL2/RP36/RB4_33") (pintype "bidirectional"))
    )
    (net (code "62") (name "SD_~{CS}") (class "Default")
      (node (ref "SD_CARD") (pin "2") (pinfunction "~{CS}/DAT3_2") (pintype "bidirectional"))
      (node (ref "U1") (pin "37") (pinfunction "AN30/SDA1/RPI52/RC4_37") (pintype "bidirectional"))
    )
    (net (code "63") (name "SPI1_MISO") (class "Default")
      (node (ref "SD_CARD") (pin "7") (pinfunction "DAT0/MISO_7") (pintype "bidirectional"))
      (node (ref "U1") (pin "35") (pinfunction "AN28/SDI1/RPI25/RA9_35") (pintype "bidirectional"))
    )
    (net (code "64") (name "SPI1_MOSI") (class "Default")
      (node (ref "SD_CARD") (pin "3") (pinfunction "CMD/MOSI_3") (pintype "bidirectional"))
      (node (ref "U1") (pin "34") (pinfunction "OA5IN+/AN24/C5IN3-/C5IN1+/SDO1/RP20/T1CK/RA4_34") (pintype "bidirectional"))
      (node (ref "U3") (pin "19") (pinfunction "D1_19") (pintype "bidirectional"))
    )
    (net (code "65") (name "SPI1_SCK") (class "Default")
      (node (ref "SD_CARD") (pin "5") (pinfunction "CLK_5") (pintype "bidirectional"))
      (node (ref "U1") (pin "36") (pinfunction "AN29/SCK1/RPI51/RC3_36") (pintype "bidirectional"))
      (node (ref "U3") (pin "18") (pinfunction "D0_18") (pintype "bidirectional"))
    )
    (net (code "66") (name "SW1") (class "Default")
      (node (ref "J1") (pin "3") (pinfunction "3_3") (pintype "bidirectional"))
      (node (ref "R9") (pin "1") (pinfunction "1_1") (pintype "passive"))
      (node (ref "SW1") (pin "1") (pinfunction "1_1") (pintype "bidirectional"))
    )
    (net (code "67") (name "SW2") (class "Default")
      (node (ref "J1") (pin "5") (pinfunction "5_5") (pintype "bidirectional"))
      (node (ref "R10") (pin "1") (pinfunction "1_1") (pintype "passive"))
      (node (ref "SW2") (pin "1") (pinfunction "1_1") (pintype "bidirectional"))
    )
    (net (code "68") (name "SW3") (class "Default")
      (node (ref "J1") (pin "7") (pinfunction "7_7") (pintype "bidirectional"))
      (node (ref "R11") (pin "1") (pinfunction "1_1") (pintype "passive"))
      (node (ref "SW3") (pin "1") (pinfunction "1_1") (pintype "bidirectional"))
    )
    (net (code "69") (name "SW4") (class "Default")
      (node (ref "J1") (pin "9") (pinfunction "9_9") (pintype "bidirectional"))
      (node (ref "R12") (pin "1") (pinfunction "1_1") (pintype "passive"))
      (node (ref "SW4") (pin "1") (pinfunction "1_1") (pintype "bidirectional"))
    )
    (net (code "70") (name "SW5") (class "Default")
      (node (ref "J1") (pin "11") (pinfunction "11_11") (pintype "bidirectional"))
      (node (ref "R13") (pin "1") (pinfunction "1_1") (pintype "passive"))
      (node (ref "SW5") (pin "1") (pinfunction "1_1") (pintype "bidirectional"))
    )
    (net (code "71") (name "UART_RX") (class "Default")
      (node (ref "J8") (pin "3") (pinfunction "3_3") (pintype "passive"))
      (node (ref "U1") (pin "32") (pinfunction "SDA2/RPI24/RA8_32") (pintype "bidirectional"))
    )
    (net (code "72") (name "UART_TX") (class "Default")
      (node (ref "J8") (pin "1") (pinfunction "1_1") (pintype "passive"))
      (node (ref "U1") (pin "41") (pinfunction "PGED2/ASDA2/RP37/RB5_41") (pintype "bidirectional"))
    )
    (net (code "73") (name "VCAP") (class "Default")
      (node (ref "C2") (pin "1") (pinfunction "1_1") (pintype "passive"))
      (node (ref "U1") (pin "7") (pinfunction "VCAP_7") (pintype "bidirectional"))
    )
    (net (code "74") (name "VCC_OLED") (class "Default")
      (node (ref "C10") (pin "1") (pinfunction "1_1") (pintype "passive"))
      (node (ref "C8") (pin "1") (pinfunction "1_1") (pintype "passive"))
      (node (ref "C9") (pin "1") (pinfunction "1_1") (pintype "passive"))
      (node (ref "D2") (pin "C") (pinfunction "C_C") (pintype "passive"))
      (node (ref "LED6") (pin "A") (pinfunction "A_A") (pintype "passive"))
      (node (ref "R5") (pin "2") (pinfunction "2_2") (pintype "passive"))
      (node (ref "TP2") (pin "P$1") (pinfunction "1_P$1") (pintype "bidirectional"))
      (node (ref "U3") (pin "28") (pinfunction "VCC_28") (pintype "bidirectional"))
    )
    (net (code "75") (name "unconnected-(SD_CARD-DAT1-Pad8)") (class "Default")
      (node (ref "SD_CARD") (pin "8") (pinfunction "DAT1_8") (pintype "bidirectional"))
    )
    (net (code "76") (name "unconnected-(SD_CARD-DAT2-Pad1)") (class "Default")
      (node (ref "SD_CARD") (pin "1") (pinfunction "DAT2_1") (pintype "bidirectional"))
    )
    (net (code "77") (name "unconnected-(U2-VREF-Pad5)") (class "Default")
      (node (ref "U2") (pin "5") (pinfunction "VREF_5") (pintype "bidirectional"))
    )
    (net (code "78") (name "unconnected-(U3-C1N-Pad5)") (class "Default")
      (node (ref "U3") (pin "5") (pinfunction "C1N_5") (pintype "bidirectional"))
    )
    (net (code "79") (name "unconnected-(U3-C1P-Pad4)") (class "Default")
      (node (ref "U3") (pin "4") (pinfunction "C1P_4") (pintype "bidirectional"))
    )
    (net (code "80") (name "unconnected-(U3-C2N-Pad3)") (class "Default")
      (node (ref "U3") (pin "3") (pinfunction "C2N_3") (pintype "bidirectional"))
    )
    (net (code "81") (name "unconnected-(U3-C2P-Pad2)") (class "Default")
      (node (ref "U3") (pin "2") (pinfunction "C2P_2") (pintype "bidirectional"))
    )
    (net (code "82") (name "unconnected-(U3-D2-Pad20)") (class "Default")
      (node (ref "U3") (pin "20") (pinfunction "D2_20") (pintype "bidirectional"))
    )
    (net (code "83") (name "~{MCLR}") (class "Default")
      (node (ref "J5") (pin "1") (pinfunction "1_1") (pintype "passive"))
      (node (ref "R16") (pin "1") (pinfunction "1_1") (pintype "passive"))
      (node (ref "U1") (pin "18") (pinfunction "~{MCLR}_18") (pintype "bidirectional"))
    )
  )
)
